# LDR.net
KiCad netlist of a schematic drawn in EAGLE
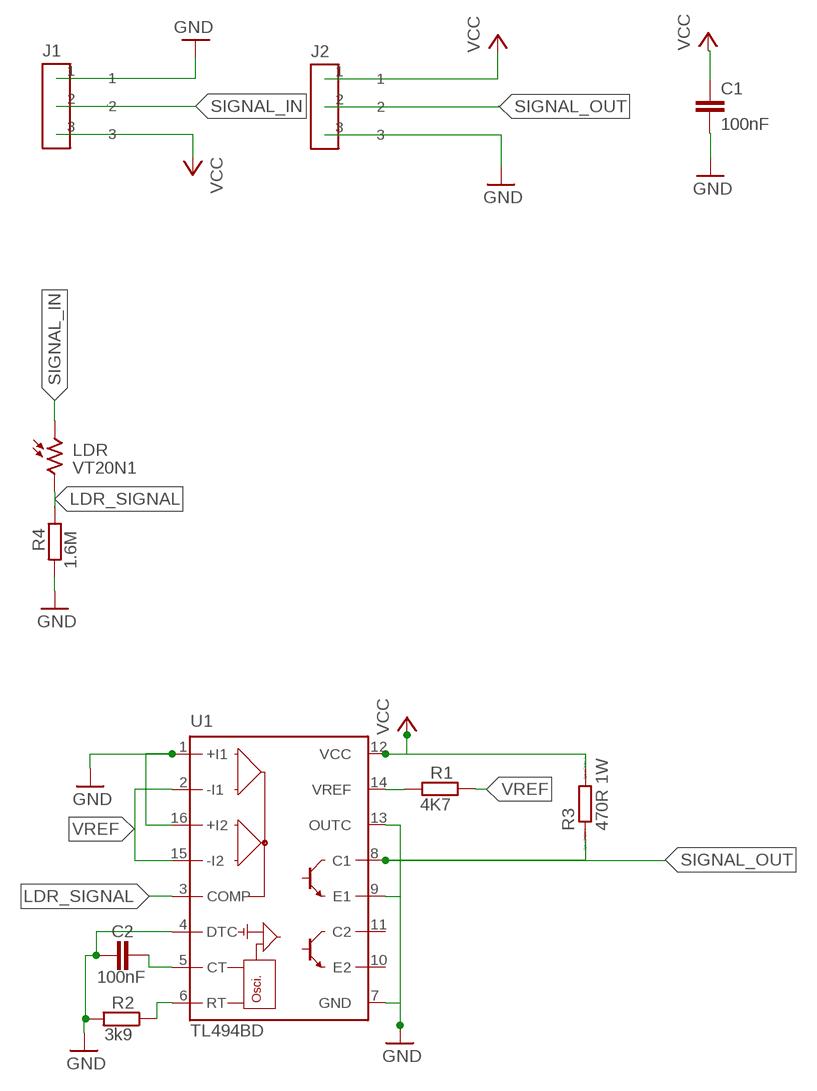
[diagram p0: schematic, sheet 1]

(export (version "E")
  (design (tool "Eeschema 10.0.6"))
  (components
    (comp (ref "C1")
      (value "100nF")
      (footprint "eagle-import:C0805")
      (libsource (lib "eagle-import") (part "C-EUC0805"))
    )
    (comp (ref "C2")
      (value "100nF")
      (footprint "eagle-import:C0805")
      (libsource (lib "eagle-import") (part "C-EUC0805"))
    )
    (comp (ref "J1")
      (value "CONECTOR_MACHO")
      (footprint "eagle-import:3CONECTOR")
      (libsource (lib "eagle-import") (part "CONECTOR_MACHO"))
    )
    (comp (ref "J2")
      (value "CONECTOR_FEMEA")
      (footprint "eagle-import:3CONECTOR")
      (libsource (lib "eagle-import") (part "CONECTOR_FEMEA"))
    )
    (comp (ref "LDR")
      (value "VT20N1")
      (footprint "eagle-import:TO46-VT200")
      (libsource (lib "eagle-import") (part "VT20N1"))
    )
    (comp (ref "R1")
      (value "4K7")
      (footprint "eagle-import:R0805W")
      (libsource (lib "eagle-import") (part "R-EU_R0805W"))
    )
    (comp (ref "R2")
      (value "3k9")
      (footprint "eagle-import:R0805W")
      (libsource (lib "eagle-import") (part "R-EU_R0805W"))
    )
    (comp (ref "R3")
      (value "470R 1W")
      (footprint "eagle-import:R2512")
      (libsource (lib "eagle-import") (part "RR2512"))
    )
    (comp (ref "R4")
      (value "1.6M")
      (footprint "eagle-import:R0805W")
      (libsource (lib "eagle-import") (part "R-EU_R0805W"))
    )
    (comp (ref "U1")
      (value "TL494BD")
      (footprint "eagle-import:SO16")
      (libsource (lib "eagle-import") (part "TL494DB"))
    )
  )
  (nets
    (net (code "1") (name "GND") (class "Default")
      (node (ref "C1") (pin "2") (pinfunction "2_2") (pintype "passive"))
      (node (ref "C2") (pin "1") (pinfunction "1_1") (pintype "passive"))
      (node (ref "J1") (pin "1") (pinfunction "1_1") (pintype "bidirectional"))
      (node (ref "J2") (pin "3") (pinfunction "3_3") (pintype "bidirectional"))
      (node (ref "R2") (pin "2") (pinfunction "2_2") (pintype "passive"))
      (node (ref "R4") (pin "2") (pinfunction "2_2") (pintype "passive"))
      (node (ref "U1") (pin "1") (pinfunction "+I1_1") (pintype "input"))
      (node (ref "U1") (pin "13") (pinfunction "OUTC_13") (pintype "output"))
      (node (ref "U1") (pin "16") (pinfunction "+I2_16") (pintype "input"))
      (node (ref "U1") (pin "4") (pinfunction "DTC_4") (pintype "input"))
      (node (ref "U1") (pin "7") (pinfunction "GND_7") (pintype "power_in"))
      (node (ref "U1") (pin "9") (pinfunction "E1_9") (pintype "passive"))
    )
    (net (code "2") (name "LDR_SIGNAL") (class "Default")
      (node (ref "LDR") (pin "2") (pinfunction "2_2") (pintype "passive"))
      (node (ref "R4") (pin "1") (pinfunction "1_1") (pintype "passive"))
      (node (ref "U1") (pin "3") (pinfunction "COMP_3") (pintype "passive"))
    )
    (net (code "3") (name "Net-(U1-CT)") (class "Default")
      (node (ref "C2") (pin "2") (pinfunction "2_2") (pintype "passive"))
      (node (ref "U1") (pin "5") (pinfunction "CT_5") (pintype "input"))
    )
    (net (code "4") (name "Net-(U1-RT)") (class "Default")
      (node (ref "R2") (pin "1") (pinfunction "1_1") (pintype "passive"))
      (node (ref "U1") (pin "6") (pinfunction "RT_6") (pintype "input"))
    )
    (net (code "5") (name "Net-(U1-VREF)") (class "Default")
      (node (ref "R1") (pin "2") (pinfunction "2_2") (pintype "passive"))
      (node (ref "U1") (pin "14") (pinfunction "VREF_14") (pintype "input"))
    )
    (net (code "6") (name "SIGNAL_IN") (class "Default")
      (node (ref "J1") (pin "2") (pinfunction "2_2") (pintype "bidirectional"))
      (node (ref "LDR") (pin "1") (pinfunction "1_1") (pintype "passive"))
    )
    (net (code "7") (name "SIGNAL_OUT") (class "Default")
      (node (ref "J2") (pin "2") (pinfunction "2_2") (pintype "bidirectional"))
      (node (ref "R3") (pin "1") (pinfunction "1_1") (pintype "passive"))
      (node (ref "U1") (pin "8") (pinfunction "C1_8") (pintype "passive"))
    )
    (net (code "8") (name "VCC") (class "Default")
      (node (ref "C1") (pin "1") (pinfunction "1_1") (pintype "passive"))
      (node (ref "J1") (pin "3") (pinfunction "3_3") (pintype "bidirectional"))
      (node (ref "J2") (pin "1") (pinfunction "1_1") (pintype "bidirectional"))
      (node (ref "R3") (pin "2") (pinfunction "2_2") (pintype "passive"))
      (node (ref "U1") (pin "12") (pinfunction "VCC_12") (pintype "power_in"))
    )
    (net (code "9") (name "VREF") (class "Default")
      (node (ref "R1") (pin "1") (pinfunction "1_1") (pintype "passive"))
      (node (ref "U1") (pin "15") (pinfunction "-I2_15") (pintype "input"))
      (node (ref "U1") (pin "2") (pinfunction "-I1_2") (pintype "input"))
    )
    (net (code "10") (name "unconnected-(U1-C2-Pad11)") (class "Default")
      (node (ref "U1") (pin "11") (pinfunction "C2_11") (pintype "passive"))
    )
    (net (code "11") (name "unconnected-(U1-E2-Pad10)") (class "Default")
      (node (ref "U1") (pin "10") (pinfunction "E2_10") (pintype "passive"))
    )
  )
)
